# Dual_signal_switch.net
KiCad netlist of a schematic drawn in Altium Designer
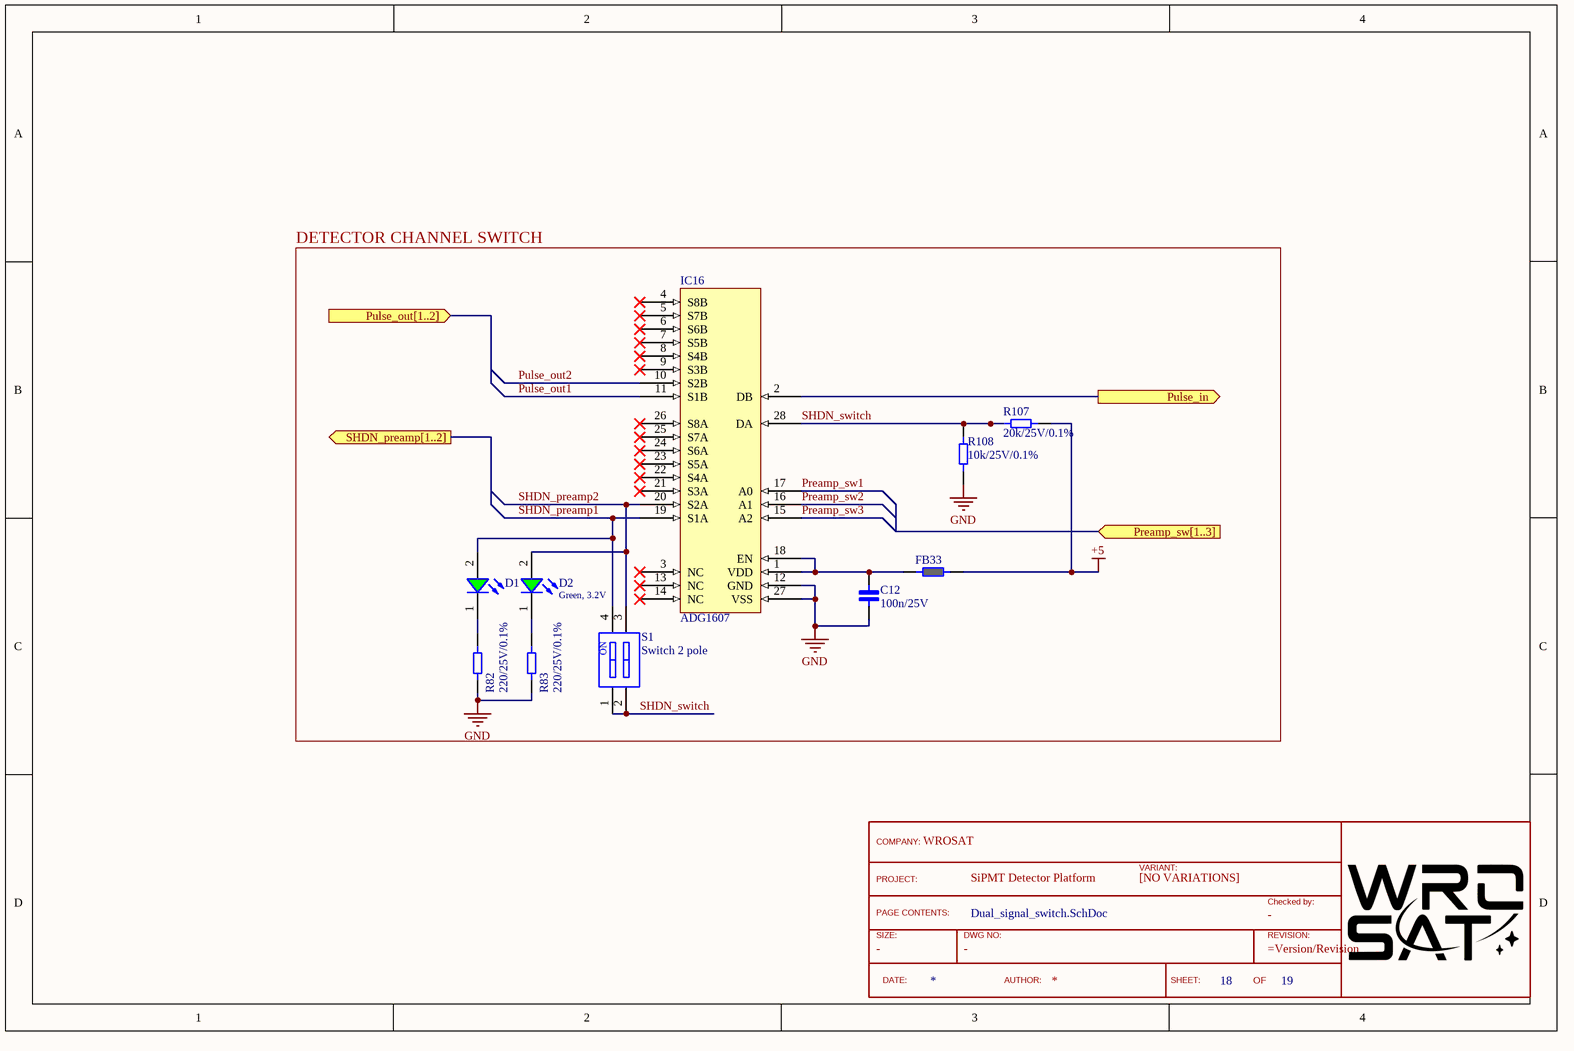
[diagram p0: Dual_signal_switch.SchDoc]

(export (version "E")
  (design (tool "Eeschema 10.0.6"))
  (components
    (comp (ref "C12")
      (value "100n/25V")
      (footprint "Cap_0402")
      (description "Ceramic Capacitor 100n / 0402 / 25V / ±5%, Wurth Elektronik MLCC")
      (libsource (lib "Cubesat_lib") (part "Cap_0402_100n"))
    )
    (comp (ref "D1")
      (value "Green, 3.2V")
      (footprint "WL-SMCW_0603_H=0.7mm")
      (description "WL-SMCW SMT Mono-color Chip LED Waterclear, size 0603, Green, 3.2V, 140deg")
      (fields (field (name "PART NUMBER") "150060GS75000") (field (name "PUBLISHER") "Wurth Elektronik"))
      (libsource (lib "LEDS") (part "150060GS75000"))
    )
    (comp (ref "D2")
      (value "Green, 3.2V")
      (footprint "WL-SMCW_0603_H=0.7mm")
      (description "WL-SMCW SMT Mono-color Chip LED Waterclear, size 0603, Green, 3.2V, 140deg")
      (fields (field (name "PART NUMBER") "150060GS75000") (field (name "PUBLISHER") "Wurth Elektronik"))
      (libsource (lib "LEDS") (part "150060GS75000"))
    )
    (comp (ref "FB33")
      (value "Ferrite_bead_0402")
      (footprint "FERRITE_0402")
      (description "Ferrite bead, wurth 74269241102")
      (libsource (lib "Cubesat_lib") (part "Ferrite_bead_0402"))
    )
    (comp (ref "IC16")
      (value "ADG1607")
      (footprint "TSOP28")
      (description "8-ch MUX")
      (libsource (lib "Cubesat_lib") (part "ADG1607"))
    )
    (comp (ref "R82")
      (value "220/25V/0.1%")
      (footprint "RES_0402")
      (description "Vishay, thin film resistor 1/25V/0.1%")
      (libsource (lib "Cubesat_lib") (part "Res_0402_1"))
    )
    (comp (ref "R83")
      (value "220/25V/0.1%")
      (footprint "RES_0402")
      (description "Vishay, thin film resistor 1/25V/0.1%")
      (libsource (lib "Cubesat_lib") (part "Res_0402_1"))
    )
    (comp (ref "R107")
      (value "20k/25V/0.1%")
      (footprint "RES_0402")
      (description "Vishay, thin film resistor 20k/25V/0.1%")
      (libsource (lib "Cubesat_lib") (part "Res_0402_20k"))
    )
    (comp (ref "R108")
      (value "10k/25V/0.1%")
      (footprint "RES_0402")
      (description "Vishay, thin film resistor 10k/25V/0.1%")
      (libsource (lib "Cubesat_lib") (part "Res_0402_10k"))
    )
    (comp (ref "S1")
      (value "Switch 2 pole")
      (footprint "Dip Switch 2")
      (description "WS-DISV Small Compact SMD Dip Switch, Flat Actuator with Top Tape, pitch 1.27mm, 2p")
      (fields (field (name "PART NUMBER") "416131160802") (field (name "PUBLISHER") "Wurth Elektronik"))
      (libsource (lib "Cubesat_lib") (part "Switch 2 pole"))
    )
  )
  (nets
    (net (code "1") (name "+5") (class "Default")
      (node (ref "FB33") (pin "2") (pinfunction "2_2") (pintype "passive"))
      (node (ref "R107") (pin "2") (pinfunction "2_2") (pintype "passive"))
    )
    (net (code "2") (name "/Preamp_sw1") (class "Default")
      (node (ref "IC16") (pin "17") (pinfunction "A0_17") (pintype "input"))
    )
    (net (code "3") (name "/Preamp_sw2") (class "Default")
      (node (ref "IC16") (pin "16") (pinfunction "A1_16") (pintype "input"))
    )
    (net (code "4") (name "/Preamp_sw3") (class "Default")
      (node (ref "IC16") (pin "15") (pinfunction "A2_15") (pintype "input"))
    )
    (net (code "6") (name "/Pulse_in") (class "Default")
      (node (ref "IC16") (pin "2") (pinfunction "DB_2") (pintype "input"))
    )
    (net (code "7") (name "/Pulse_out1") (class "Default")
      (node (ref "IC16") (pin "11") (pinfunction "S1B_11") (pintype "input"))
    )
    (net (code "8") (name "/Pulse_out2") (class "Default")
      (node (ref "IC16") (pin "10") (pinfunction "S2B_10") (pintype "input"))
    )
    (net (code "10") (name "/SHDN_preamp1") (class "Default")
      (node (ref "D1") (pin "2") (pinfunction "A_2") (pintype "passive"))
      (node (ref "IC16") (pin "19") (pinfunction "S1A_19") (pintype "input"))
      (node (ref "S1") (pin "4") (pinfunction "4_4") (pintype "passive"))
    )
    (net (code "11") (name "/SHDN_preamp2") (class "Default")
      (node (ref "D2") (pin "2") (pinfunction "A_2") (pintype "passive"))
      (node (ref "IC16") (pin "20") (pinfunction "S2A_20") (pintype "input"))
      (node (ref "S1") (pin "3") (pinfunction "3_3") (pintype "passive"))
    )
    (net (code "13") (name "/SHDN_switch") (class "Default")
      (node (ref "IC16") (pin "28") (pinfunction "DA_28") (pintype "input"))
      (node (ref "R107") (pin "1") (pinfunction "1_1") (pintype "passive"))
      (node (ref "R108") (pin "2") (pinfunction "2_2") (pintype "passive"))
      (node (ref "S1") (pin "1") (pinfunction "1_1") (pintype "passive"))
      (node (ref "S1") (pin "2") (pinfunction "2_2") (pintype "passive"))
    )
    (net (code "14") (name "GND") (class "Default")
      (node (ref "C12") (pin "1") (pinfunction "1_1") (pintype "passive"))
      (node (ref "IC16") (pin "12") (pinfunction "GND_12") (pintype "input"))
      (node (ref "IC16") (pin "27") (pinfunction "VSS_27") (pintype "input"))
      (node (ref "R108") (pin "1") (pinfunction "1_1") (pintype "passive"))
      (node (ref "R82") (pin "1") (pinfunction "1_1") (pintype "passive"))
      (node (ref "R83") (pin "1") (pinfunction "1_1") (pintype "passive"))
    )
    (net (code "15") (name "Net-(D1-K)") (class "Default")
      (node (ref "D1") (pin "1") (pinfunction "K_1") (pintype "passive"))
      (node (ref "R82") (pin "2") (pinfunction "2_2") (pintype "passive"))
    )
    (net (code "16") (name "Net-(D2-K)") (class "Default")
      (node (ref "D2") (pin "1") (pinfunction "K_1") (pintype "passive"))
      (node (ref "R83") (pin "2") (pinfunction "2_2") (pintype "passive"))
    )
    (net (code "17") (name "Net-(IC16-EN)") (class "Default")
      (node (ref "C12") (pin "2") (pinfunction "2_2") (pintype "passive"))
      (node (ref "FB33") (pin "1") (pinfunction "1_1") (pintype "passive"))
      (node (ref "IC16") (pin "1") (pinfunction "VDD_1") (pintype "input"))
      (node (ref "IC16") (pin "18") (pinfunction "EN_18") (pintype "input"))
    )
    (net (code "18") (name "unconnected-(IC16-NC-Pad3)") (class "Default")
      (node (ref "IC16") (pin "3") (pinfunction "NC_3") (pintype "input+no_connect"))
    )
    (net (code "19") (name "unconnected-(IC16-NC-Pad13)") (class "Default")
      (node (ref "IC16") (pin "13") (pinfunction "NC_13") (pintype "input+no_connect"))
    )
    (net (code "20") (name "unconnected-(IC16-NC-Pad14)") (class "Default")
      (node (ref "IC16") (pin "14") (pinfunction "NC_14") (pintype "input+no_connect"))
    )
    (net (code "21") (name "unconnected-(IC16-S3A-Pad21)") (class "Default")
      (node (ref "IC16") (pin "21") (pinfunction "S3A_21") (pintype "input+no_connect"))
    )
    (net (code "22") (name "unconnected-(IC16-S3B-Pad9)") (class "Default")
      (node (ref "IC16") (pin "9") (pinfunction "S3B_9") (pintype "input+no_connect"))
    )
    (net (code "23") (name "unconnected-(IC16-S4A-Pad22)") (class "Default")
      (node (ref "IC16") (pin "22") (pinfunction "S4A_22") (pintype "input+no_connect"))
    )
    (net (code "24") (name "unconnected-(IC16-S4B-Pad8)") (class "Default")
      (node (ref "IC16") (pin "8") (pinfunction "S4B_8") (pintype "input+no_connect"))
    )
    (net (code "25") (name "unconnected-(IC16-S5A-Pad23)") (class "Default")
      (node (ref "IC16") (pin "23") (pinfunction "S5A_23") (pintype "input+no_connect"))
    )
    (net (code "26") (name "unconnected-(IC16-S5B-Pad7)") (class "Default")
      (node (ref "IC16") (pin "7") (pinfunction "S5B_7") (pintype "input+no_connect"))
    )
    (net (code "27") (name "unconnected-(IC16-S6A-Pad24)") (class "Default")
      (node (ref "IC16") (pin "24") (pinfunction "S6A_24") (pintype "input+no_connect"))
    )
    (net (code "28") (name "unconnected-(IC16-S6B-Pad6)") (class "Default")
      (node (ref "IC16") (pin "6") (pinfunction "S6B_6") (pintype "input+no_connect"))
    )
    (net (code "29") (name "unconnected-(IC16-S7A-Pad25)") (class "Default")
      (node (ref "IC16") (pin "25") (pinfunction "S7A_25") (pintype "input+no_connect"))
    )
    (net (code "30") (name "unconnected-(IC16-S7B-Pad5)") (class "Default")
      (node (ref "IC16") (pin "5") (pinfunction "S7B_5") (pintype "input+no_connect"))
    )
    (net (code "31") (name "unconnected-(IC16-S8A-Pad26)") (class "Default")
      (node (ref "IC16") (pin "26") (pinfunction "S8A_26") (pintype "input+no_connect"))
    )
    (net (code "32") (name "unconnected-(IC16-S8B-Pad4)") (class "Default")
      (node (ref "IC16") (pin "4") (pinfunction "S8B_4") (pintype "input+no_connect"))
    )
  )
)
